# RouterBatteryLED.net
KiCad netlist of a schematic drawn in Altium Designer
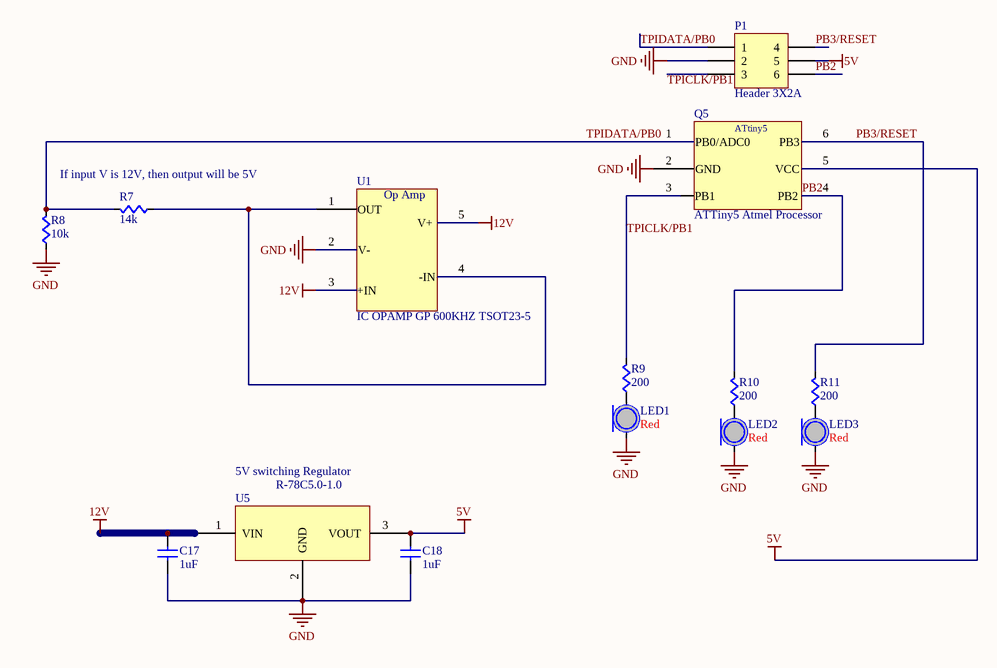
[diagram p0: RouterBatteryLED.SchDoc]

(export (version "E")
  (design (tool "Eeschema 10.0.6"))
  (components
    (comp (ref "C17")
      (value "1uF")
      (footprint "CAPC0603")
      (fields (field (name "Comment") "Cap"))
      (libsource (lib "SubjuGator8") (part "Cap"))
    )
    (comp (ref "C18")
      (value "1uF")
      (footprint "CAPC0603")
      (fields (field (name "Comment") "Cap"))
      (libsource (lib "SubjuGator8") (part "Cap"))
    )
    (comp (ref "LED1")
      (value "LED")
      (footprint "LED0603")
      (fields (field (name "COLOR") "Red"))
      (libsource (lib "SubjuGator8") (part "LED"))
    )
    (comp (ref "LED2")
      (value "LED")
      (footprint "LED0603")
      (fields (field (name "COLOR") "Red"))
      (libsource (lib "SubjuGator8") (part "LED"))
    )
    (comp (ref "LED3")
      (value "LED")
      (footprint "LED0603")
      (fields (field (name "COLOR") "Red"))
      (libsource (lib "SubjuGator8") (part "LED"))
    )
    (comp (ref "P1")
      (value "Header 3X2A")
      (footprint "HDR2X3_CEN")
      (description "Header, 3-Pin, Dual row")
      (fields (field (name "PUBLISHER") "Altium Limited"))
      (libsource (lib "Miscellaneous Connectors") (part "Header 3X2A"))
    )
    (comp (ref "Q5")
      (value "ATTiny5 Atmel Processor")
      (footprint "ATTiny5")
      (fields
        (field (name "DIGIKEY PART NUMBER") "ATTiny5-TSHRCT-ND")
        (field (name "MANUFACTURER PART #") "ATTINY5-TSHR")
      )
      (libsource (lib "SubjuGator8") (part "ATTiny5 Atmel Processor"))
    )
    (comp (ref "R7")
      (value "14k")
      (footprint "RES0603")
      (fields (field (name "Comment") "Res"))
      (libsource (lib "SubjuGator8") (part "Res"))
    )
    (comp (ref "R8")
      (value "10k")
      (footprint "RES0603")
      (fields (field (name "Comment") "Res"))
      (libsource (lib "SubjuGator8") (part "Res"))
    )
    (comp (ref "R9")
      (value "200")
      (footprint "RES0603")
      (fields (field (name "Comment") "Res"))
      (libsource (lib "SubjuGator8") (part "Res"))
    )
    (comp (ref "R10")
      (value "200")
      (footprint "RES0603")
      (fields (field (name "Comment") "Res"))
      (libsource (lib "SubjuGator8") (part "Res"))
    )
    (comp (ref "R11")
      (value "200")
      (footprint "RES0603")
      (fields (field (name "Comment") "Res"))
      (libsource (lib "SubjuGator8") (part "Res"))
    )
    (comp (ref "U1")
      (value "IC OPAMP GP 600KHZ TSOT23-5")
      (footprint "SOT95P280X100-5N")
      (fields
        (field (name "DIGIKEY PART #") "AD8677AUJZ-REEL7CT-ND")
        (field (name "MANUFACTURER PART #") "AD8677AUJZ-REEL7")
      )
      (libsource (lib "SubjuGator8") (part "IC OPAMP GP 600KHZ TSOT23-5"))
    )
    (comp (ref "U5")
      (value "R-78C5.0-1.0")
      (footprint "R-78C5.0-1.0")
      (description "CONV DC/DC 1A 5V OUT SIP VERT")
      (libsource (lib "SubjuGator8") (part "R-78C5.0-1.0"))
    )
  )
  (nets
    (net (code "1") (name "/PB2") (class "Default")
      (node (ref "P1") (pin "6") (pinfunction "6_6") (pintype "passive"))
      (node (ref "Q5") (pin "4") (pinfunction "PB2_4") (pintype "passive"))
      (node (ref "R10") (pin "1") (pinfunction "A_1") (pintype "passive"))
    )
    (net (code "2") (name "/PB3{slash}RESET") (class "Default")
      (node (ref "P1") (pin "4") (pinfunction "4_4") (pintype "passive"))
      (node (ref "Q5") (pin "6") (pinfunction "PB3_6") (pintype "passive"))
      (node (ref "R11") (pin "1") (pinfunction "A_1") (pintype "passive"))
    )
    (net (code "3") (name "/TPICLK{slash}PB1") (class "Default")
      (node (ref "R9") (pin "1") (pinfunction "A_1") (pintype "passive"))
    )
    (net (code "4") (name "/TPIDATA{slash}PB0") (class "Default")
      (node (ref "P1") (pin "1") (pinfunction "1_1") (pintype "passive"))
      (node (ref "Q5") (pin "1") (pinfunction "PB0/ADC0_1") (pintype "passive"))
      (node (ref "R7") (pin "1") (pinfunction "A_1") (pintype "passive"))
      (node (ref "R8") (pin "1") (pinfunction "A_1") (pintype "passive"))
    )
    (net (code "5") (name "5V") (class "Default")
      (node (ref "C18") (pin "1") (pinfunction "A_1") (pintype "passive"))
      (node (ref "P1") (pin "5") (pinfunction "5_5") (pintype "passive"))
      (node (ref "Q5") (pin "5") (pinfunction "VCC_5") (pintype "passive"))
      (node (ref "U5") (pin "3") (pinfunction "VOUT_3") (pintype "passive"))
    )
    (net (code "6") (name "12V") (class "Default")
      (node (ref "C17") (pin "1") (pinfunction "A_1") (pintype "passive"))
      (node (ref "U1") (pin "3") (pinfunction "+IN_3") (pintype "passive"))
      (node (ref "U1") (pin "5") (pinfunction "V+_5") (pintype "passive"))
      (node (ref "U5") (pin "1") (pinfunction "VIN_1") (pintype "passive"))
    )
    (net (code "7") (name "GND") (class "Default")
      (node (ref "C17") (pin "2") (pinfunction "B_2") (pintype "passive"))
      (node (ref "C18") (pin "2") (pinfunction "B_2") (pintype "passive"))
      (node (ref "LED1") (pin "C") (pinfunction "C_C") (pintype "passive"))
      (node (ref "LED2") (pin "C") (pinfunction "C_C") (pintype "passive"))
      (node (ref "LED3") (pin "C") (pinfunction "C_C") (pintype "passive"))
      (node (ref "P1") (pin "2") (pinfunction "2_2") (pintype "passive"))
      (node (ref "R8") (pin "2") (pinfunction "B_2") (pintype "passive"))
      (node (ref "U1") (pin "2") (pinfunction "V-_2") (pintype "passive"))
      (node (ref "U5") (pin "2") (pinfunction "GND_2") (pintype "power_in"))
    )
    (net (code "8") (name "Net-(R7-B)") (class "Default")
      (node (ref "R7") (pin "2") (pinfunction "B_2") (pintype "passive"))
      (node (ref "U1") (pin "4") (pinfunction "-IN_4") (pintype "passive"))
    )
    (net (code "9") (name "Net-(R9-B)") (class "Default")
      (node (ref "LED1") (pin "A") (pinfunction "A_A") (pintype "passive"))
      (node (ref "R9") (pin "2") (pinfunction "B_2") (pintype "passive"))
    )
    (net (code "10") (name "Net-(R10-B)") (class "Default")
      (node (ref "LED2") (pin "A") (pinfunction "A_A") (pintype "passive"))
      (node (ref "R10") (pin "2") (pinfunction "B_2") (pintype "passive"))
    )
    (net (code "11") (name "Net-(R11-B)") (class "Default")
      (node (ref "LED3") (pin "A") (pinfunction "A_A") (pintype "passive"))
      (node (ref "R11") (pin "2") (pinfunction "B_2") (pintype "passive"))
    )
    (net (code "12") (name "unconnected-(P1-Pad3)") (class "Default")
      (node (ref "P1") (pin "3") (pinfunction "3_3") (pintype "passive"))
    )
    (net (code "13") (name "unconnected-(Q5-GND-Pad2)") (class "Default")
      (node (ref "Q5") (pin "2") (pinfunction "GND_2") (pintype "passive"))
    )
    (net (code "14") (name "unconnected-(Q5-PB1-Pad3)") (class "Default")
      (node (ref "Q5") (pin "3") (pinfunction "PB1_3") (pintype "passive"))
    )
    (net (code "15") (name "unconnected-(U1-OUT-Pad1)") (class "Default")
      (node (ref "U1") (pin "1") (pinfunction "OUT_1") (pintype "passive"))
    )
  )
)
